# Calc_V4_Final.net
KiCad netlist of a schematic drawn in EAGLE
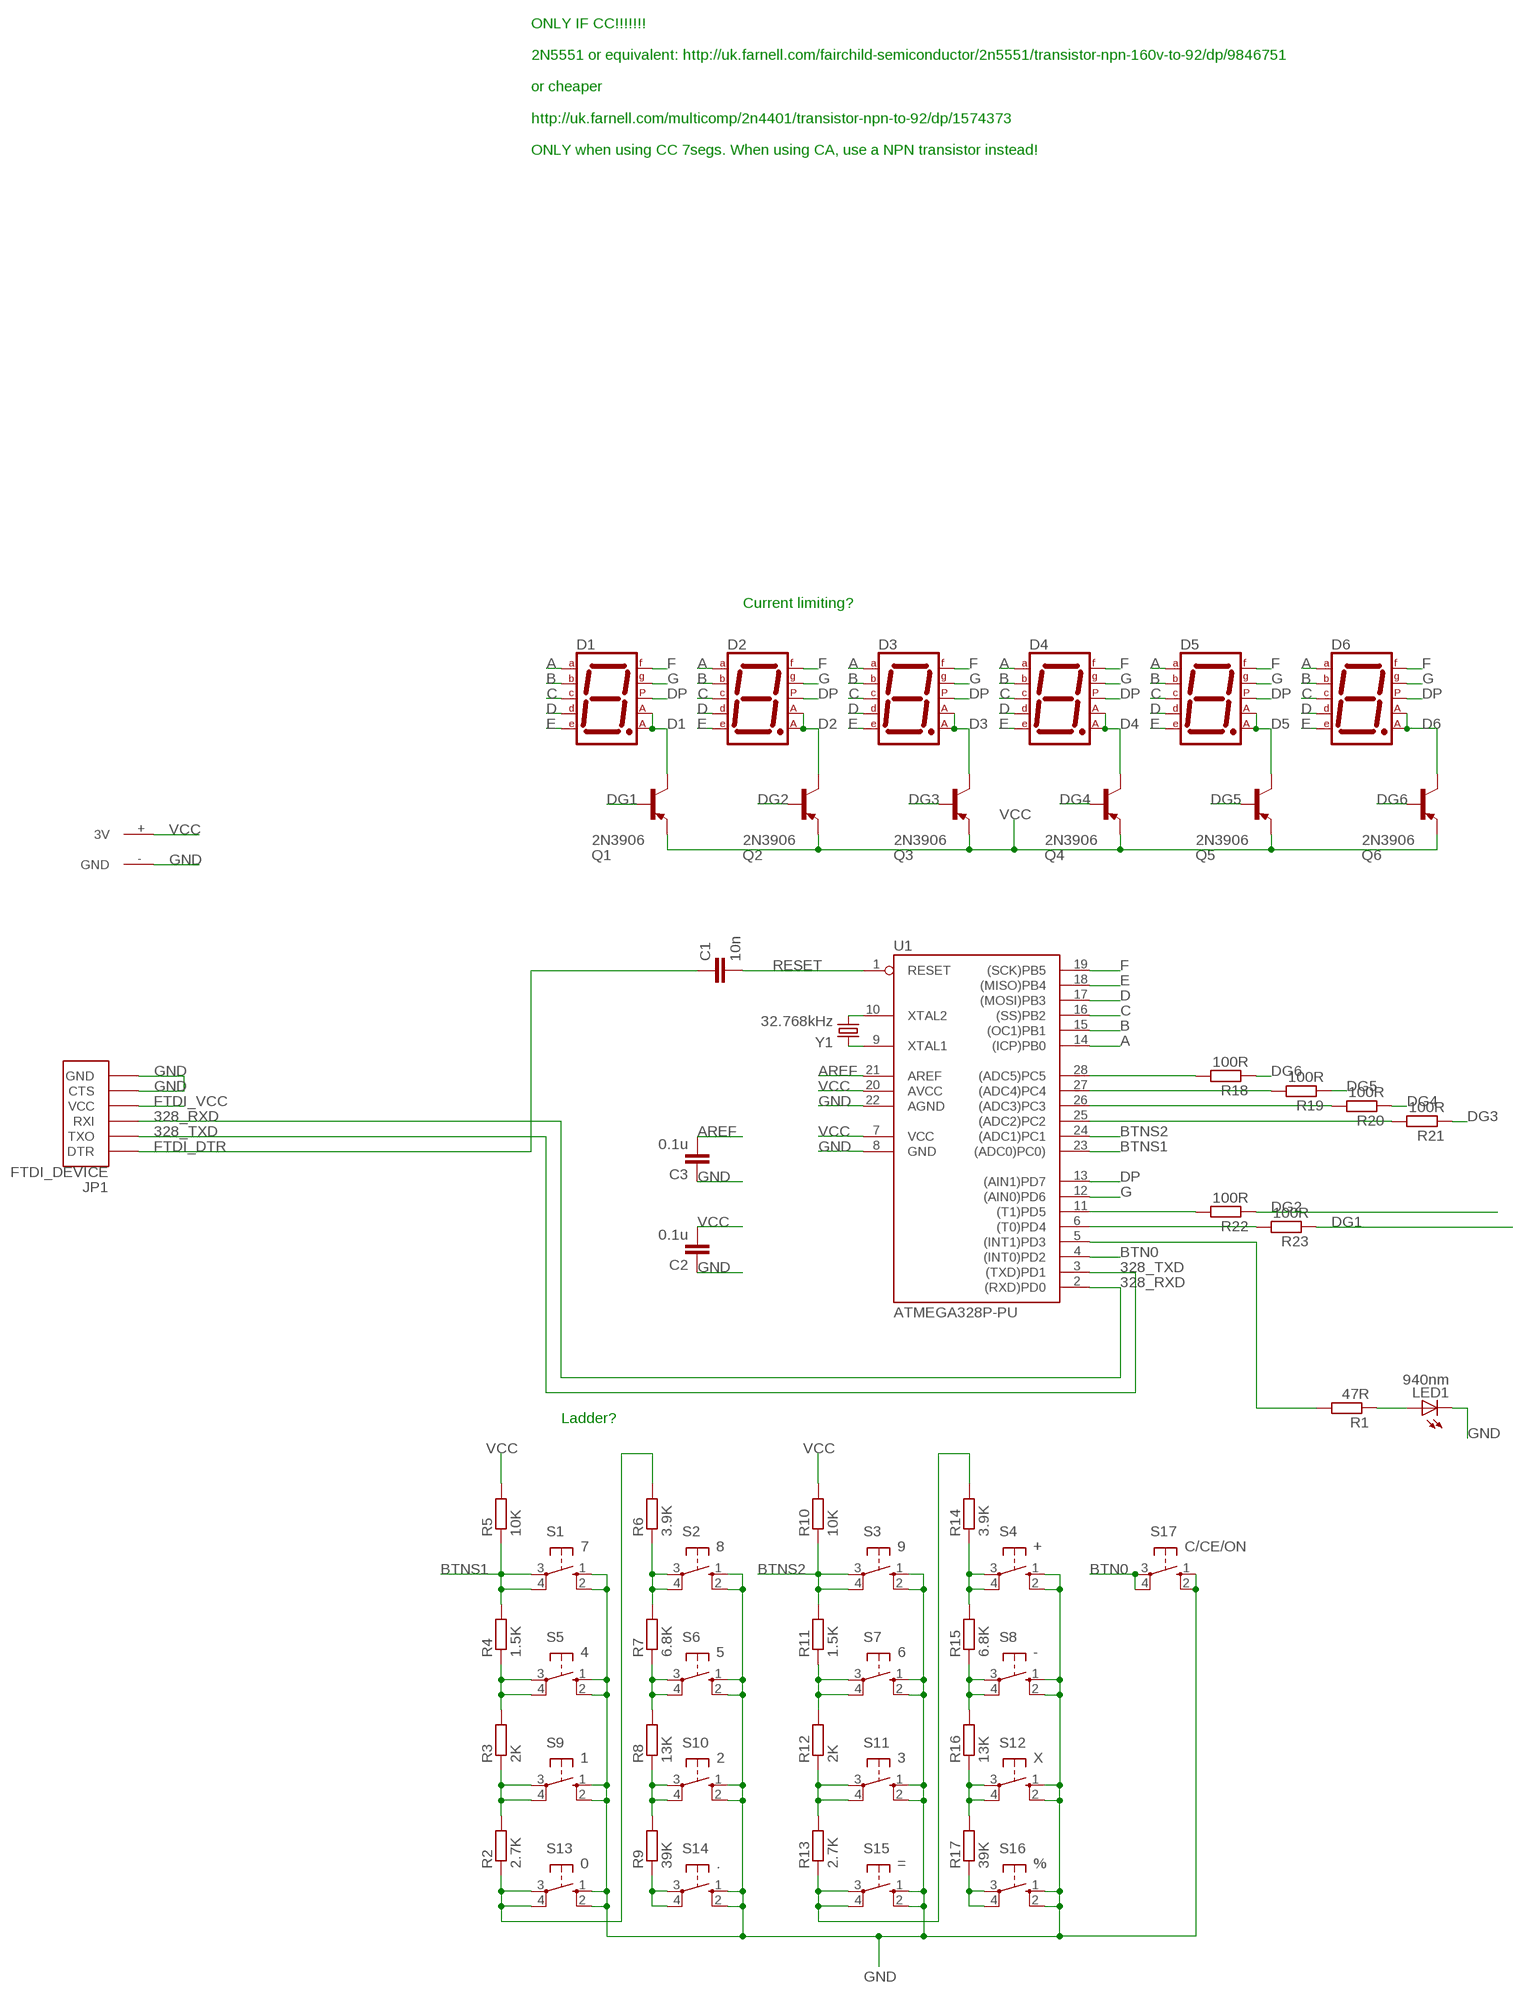
[diagram p0: schematic, sheet 1]

(export (version "E")
  (design (tool "Eeschema 10.0.6"))
  (components
    (comp (ref "C1")
      (value "10n")
      (footprint "eagle-import:C025-024X044")
      (libsource (lib "eagle-import") (part "C-EU025-024X044"))
    )
    (comp (ref "C2")
      (value "0.1u")
      (footprint "eagle-import:C025-024X044")
      (libsource (lib "eagle-import") (part "C-EU025-024X044"))
    )
    (comp (ref "C3")
      (value "0.1u")
      (footprint "eagle-import:C025-024X044")
      (libsource (lib "eagle-import") (part "C-EU025-024X044"))
    )
    (comp (ref "D1")
      (value "7SEG-MCA")
      (footprint "eagle-import:7SEG-7")
      (libsource (lib "eagle-import") (part "7SEG-MCA"))
    )
    (comp (ref "D2")
      (value "7SEG-MCA")
      (footprint "eagle-import:7SEG-7")
      (libsource (lib "eagle-import") (part "7SEG-MCA"))
    )
    (comp (ref "D3")
      (value "7SEG-MCA")
      (footprint "eagle-import:7SEG-7")
      (libsource (lib "eagle-import") (part "7SEG-MCA"))
    )
    (comp (ref "D4")
      (value "7SEG-MCA")
      (footprint "eagle-import:7SEG-7")
      (libsource (lib "eagle-import") (part "7SEG-MCA"))
    )
    (comp (ref "D5")
      (value "7SEG-MCA")
      (footprint "eagle-import:7SEG-7")
      (libsource (lib "eagle-import") (part "7SEG-MCA"))
    )
    (comp (ref "D6")
      (value "7SEG-MCA")
      (footprint "eagle-import:7SEG-7")
      (libsource (lib "eagle-import") (part "7SEG-MCA"))
    )
    (comp (ref "JP1")
      (value "FTDI_DEVICE")
      (footprint "eagle-import:FTDI_DEVICE_SIDE")
      (libsource (lib "eagle-import") (part "FTDI_DEVICE"))
    )
    (comp (ref "LED1")
      (value "940nm")
      (footprint "eagle-import:LED5MM")
      (libsource (lib "eagle-import") (part "LED5MM"))
    )
    (comp (ref "Q1")
      (value "2N3906")
      (footprint "eagle-import:TO92")
      (libsource (lib "eagle-import") (part "2N3906"))
    )
    (comp (ref "Q2")
      (value "2N3906")
      (footprint "eagle-import:TO92")
      (libsource (lib "eagle-import") (part "2N3906"))
    )
    (comp (ref "Q3")
      (value "2N3906")
      (footprint "eagle-import:TO92")
      (libsource (lib "eagle-import") (part "2N3906"))
    )
    (comp (ref "Q4")
      (value "2N3906")
      (footprint "eagle-import:TO92")
      (libsource (lib "eagle-import") (part "2N3906"))
    )
    (comp (ref "Q5")
      (value "2N3906")
      (footprint "eagle-import:TO92")
      (libsource (lib "eagle-import") (part "2N3906"))
    )
    (comp (ref "Q6")
      (value "2N3906")
      (footprint "eagle-import:TO92")
      (libsource (lib "eagle-import") (part "2N3906"))
    )
    (comp (ref "R1")
      (value "47R")
      (footprint "eagle-import:0207_10")
      (libsource (lib "eagle-import") (part "R-EU_0207/10"))
    )
    (comp (ref "R2")
      (value "2.7K")
      (footprint "eagle-import:0207_10")
      (libsource (lib "eagle-import") (part "R-EU_0207/10"))
    )
    (comp (ref "R3")
      (value "2K")
      (footprint "eagle-import:0207_10")
      (libsource (lib "eagle-import") (part "R-EU_0207/10"))
    )
    (comp (ref "R4")
      (value "1.5K")
      (footprint "eagle-import:0207_10")
      (libsource (lib "eagle-import") (part "R-EU_0207/10"))
    )
    (comp (ref "R5")
      (value "10K")
      (footprint "eagle-import:0207_10")
      (libsource (lib "eagle-import") (part "R-EU_0207/10"))
    )
    (comp (ref "R6")
      (value "3.9K")
      (footprint "eagle-import:0207_10")
      (libsource (lib "eagle-import") (part "R-EU_0207/10"))
    )
    (comp (ref "R7")
      (value "6.8K")
      (footprint "eagle-import:0207_10")
      (libsource (lib "eagle-import") (part "R-EU_0207/10"))
    )
    (comp (ref "R8")
      (value "13K")
      (footprint "eagle-import:0207_10")
      (libsource (lib "eagle-import") (part "R-EU_0207/10"))
    )
    (comp (ref "R9")
      (value "39K")
      (footprint "eagle-import:0207_10")
      (libsource (lib "eagle-import") (part "R-EU_0207/10"))
    )
    (comp (ref "R10")
      (value "10K")
      (footprint "eagle-import:0207_10")
      (libsource (lib "eagle-import") (part "R-EU_0207/10"))
    )
    (comp (ref "R11")
      (value "1.5K")
      (footprint "eagle-import:0207_10")
      (libsource (lib "eagle-import") (part "R-EU_0207/10"))
    )
    (comp (ref "R12")
      (value "2K")
      (footprint "eagle-import:0207_10")
      (libsource (lib "eagle-import") (part "R-EU_0207/10"))
    )
    (comp (ref "R13")
      (value "2.7K")
      (footprint "eagle-import:0207_10")
      (libsource (lib "eagle-import") (part "R-EU_0207/10"))
    )
    (comp (ref "R14")
      (value "3.9K")
      (footprint "eagle-import:0207_10")
      (libsource (lib "eagle-import") (part "R-EU_0207/10"))
    )
    (comp (ref "R15")
      (value "6.8K")
      (footprint "eagle-import:0207_10")
      (libsource (lib "eagle-import") (part "R-EU_0207/10"))
    )
    (comp (ref "R16")
      (value "13K")
      (footprint "eagle-import:0207_10")
      (libsource (lib "eagle-import") (part "R-EU_0207/10"))
    )
    (comp (ref "R17")
      (value "39K")
      (footprint "eagle-import:0207_10")
      (libsource (lib "eagle-import") (part "R-EU_0207/10"))
    )
    (comp (ref "R18")
      (value "100R")
      (footprint "eagle-import:0207_7")
      (libsource (lib "eagle-import") (part "R-EU_0207/7"))
    )
    (comp (ref "R19")
      (value "100R")
      (footprint "eagle-import:0207_7")
      (libsource (lib "eagle-import") (part "R-EU_0207/7"))
    )
    (comp (ref "R20")
      (value "100R")
      (footprint "eagle-import:0207_7")
      (libsource (lib "eagle-import") (part "R-EU_0207/7"))
    )
    (comp (ref "R21")
      (value "100R")
      (footprint "eagle-import:0207_7")
      (libsource (lib "eagle-import") (part "R-EU_0207/7"))
    )
    (comp (ref "R22")
      (value "100R")
      (footprint "eagle-import:0207_7")
      (libsource (lib "eagle-import") (part "R-EU_0207/7"))
    )
    (comp (ref "R23")
      (value "100R")
      (footprint "eagle-import:0207_7")
      (libsource (lib "eagle-import") (part "R-EU_0207/7"))
    )
    (comp (ref "S1")
      (value "7")
      (footprint "eagle-import:B3F-10XX")
      (fields (field (name "MPN") "B3F-1000"))
      (libsource (lib "eagle-import") (part "10-XX"))
    )
    (comp (ref "S2")
      (value "8")
      (footprint "eagle-import:B3F-10XX")
      (fields
        (field (name "MPN") "B3F-1000")
        (field (name "MPN_1") "B3F-1000")
        (field (name "OC_FARNELL") "176432")
        (field (name "OC_NEWARK") "36M3542")
      )
      (libsource (lib "eagle-import") (part "10-XX"))
    )
    (comp (ref "S3")
      (value "9")
      (footprint "eagle-import:B3F-10XX")
      (fields
        (field (name "MPN") "B3F-1000")
        (field (name "MPN_1") "B3F-1000")
        (field (name "OC_FARNELL") "176432")
        (field (name "OC_NEWARK") "36M3542")
      )
      (libsource (lib "eagle-import") (part "10-XX"))
    )
    (comp (ref "S4")
      (value "+")
      (footprint "eagle-import:B3F-10XX")
      (fields
        (field (name "MPN") "B3F-1000")
        (field (name "MPN_1") "B3F-1000")
        (field (name "OC_FARNELL") "176432")
        (field (name "OC_NEWARK") "36M3542")
      )
      (libsource (lib "eagle-import") (part "10-XX"))
    )
    (comp (ref "S5")
      (value "4")
      (footprint "eagle-import:B3F-10XX")
      (fields
        (field (name "MPN") "B3F-1000")
        (field (name "MPN_1") "B3F-1000")
        (field (name "OC_FARNELL") "176432")
        (field (name "OC_NEWARK") "36M3542")
      )
      (libsource (lib "eagle-import") (part "10-XX"))
    )
    (comp (ref "S6")
      (value "5")
      (footprint "eagle-import:B3F-10XX")
      (fields
        (field (name "MPN") "B3F-1000")
        (field (name "MPN_1") "B3F-1000")
        (field (name "OC_FARNELL") "176432")
        (field (name "OC_NEWARK") "36M3542")
      )
      (libsource (lib "eagle-import") (part "10-XX"))
    )
    (comp (ref "S7")
      (value "6")
      (footprint "eagle-import:B3F-10XX")
      (fields
        (field (name "MPN") "B3F-1000")
        (field (name "MPN_1") "B3F-1000")
        (field (name "OC_FARNELL") "176432")
        (field (name "OC_NEWARK") "36M3542")
      )
      (libsource (lib "eagle-import") (part "10-XX"))
    )
    (comp (ref "S8")
      (value "-")
      (footprint "eagle-import:B3F-10XX")
      (fields
        (field (name "MPN") "B3F-1000")
        (field (name "MPN_1") "B3F-1000")
        (field (name "OC_FARNELL") "176432")
        (field (name "OC_NEWARK") "36M3542")
      )
      (libsource (lib "eagle-import") (part "10-XX"))
    )
    (comp (ref "S9")
      (value "1")
      (footprint "eagle-import:B3F-10XX")
      (fields (field (name "MPN") "B3F-1000"))
      (libsource (lib "eagle-import") (part "10-XX"))
    )
    (comp (ref "S10")
      (value "2")
      (footprint "eagle-import:B3F-10XX")
      (fields
        (field (name "MPN") "B3F-1000")
        (field (name "MPN_1") "B3F-1000")
        (field (name "OC_FARNELL") "176432")
        (field (name "OC_NEWARK") "36M3542")
      )
      (libsource (lib "eagle-import") (part "10-XX"))
    )
    (comp (ref "S11")
      (value "3")
      (footprint "eagle-import:B3F-10XX")
      (fields
        (field (name "MPN") "B3F-1000")
        (field (name "MPN_1") "B3F-1000")
        (field (name "OC_FARNELL") "176432")
        (field (name "OC_NEWARK") "36M3542")
      )
      (libsource (lib "eagle-import") (part "10-XX"))
    )
    (comp (ref "S12")
      (value "X")
      (footprint "eagle-import:B3F-10XX")
      (fields
        (field (name "MPN") "B3F-1000")
        (field (name "MPN_1") "B3F-1000")
        (field (name "OC_FARNELL") "176432")
        (field (name "OC_NEWARK") "36M3542")
      )
      (libsource (lib "eagle-import") (part "10-XX"))
    )
    (comp (ref "S13")
      (value "0")
      (footprint "eagle-import:B3F-10XX")
      (fields
        (field (name "MPN") "B3F-1000")
        (field (name "MPN_1") "B3F-1000")
        (field (name "OC_FARNELL") "176432")
        (field (name "OC_NEWARK") "36M3542")
      )
      (libsource (lib "eagle-import") (part "10-XX"))
    )
    (comp (ref "S14")
      (value ".")
      (footprint "eagle-import:B3F-10XX")
      (fields
        (field (name "MPN") "B3F-1000")
        (field (name "MPN_1") "B3F-1000")
        (field (name "OC_FARNELL") "176432")
        (field (name "OC_NEWARK") "36M3542")
      )
      (libsource (lib "eagle-import") (part "10-XX"))
    )
    (comp (ref "S15")
      (value "=")
      (footprint "eagle-import:B3F-10XX")
      (fields
        (field (name "MPN") "B3F-1000")
        (field (name "MPN_1") "B3F-1000")
        (field (name "OC_FARNELL") "176432")
        (field (name "OC_NEWARK") "36M3542")
      )
      (libsource (lib "eagle-import") (part "10-XX"))
    )
    (comp (ref "S16")
      (value "%")
      (footprint "eagle-import:B3F-10XX")
      (fields
        (field (name "MPN") "B3F-1000")
        (field (name "MPN_1") "B3F-1000")
        (field (name "OC_FARNELL") "176432")
        (field (name "OC_NEWARK") "36M3542")
      )
      (libsource (lib "eagle-import") (part "10-XX"))
    )
    (comp (ref "S17")
      (value "C/CE/ON")
      (footprint "eagle-import:B3F-10XX")
      (fields
        (field (name "MPN") "B3F-1000")
        (field (name "MPN_1") "B3F-1000")
        (field (name "OC_FARNELL") "176432")
        (field (name "OC_NEWARK") "36M3542")
      )
      (libsource (lib "eagle-import") (part "10-XX"))
    )
    (comp (ref "U$1")
      (value "AAA-BATTERY")
      (footprint "eagle-import:AAA-BATTERY-CONTACT")
      (libsource (lib "eagle-import") (part "AAA-BATTERY"))
    )
    (comp (ref "U1")
      (value "ATMEGA328P-PU")
      (footprint "eagle-import:DIL28-3")
      (libsource (lib "eagle-import") (part "ATMEGA328P-PU"))
    )
    (comp (ref "Y1")
      (value "32.768kHz")
      (footprint "eagle-import:TC26HEZ")
      (libsource (lib "eagle-import") (part "CRYSTALTC26H_EZ"))
    )
  )
  (nets
    (net (code "1") (name "/328_RXD") (class "Default")
      (node (ref "JP1") (pin "P$3") (pinfunction "RXI_P$3") (pintype "bidirectional"))
      (node (ref "U1") (pin "2") (pinfunction "(RXD)PD0_2") (pintype "bidirectional"))
    )
    (net (code "2") (name "/328_TXD") (class "Default")
      (node (ref "JP1") (pin "P$2") (pinfunction "TXO_P$2") (pintype "bidirectional"))
      (node (ref "U1") (pin "3") (pinfunction "(TXD)PD1_3") (pintype "bidirectional"))
    )
    (net (code "3") (name "/A") (class "Default")
      (node (ref "D1") (pin "10") (pinfunction "A_10") (pintype "passive"))
      (node (ref "D2") (pin "10") (pinfunction "A_10") (pintype "passive"))
      (node (ref "D3") (pin "10") (pinfunction "A_10") (pintype "passive"))
      (node (ref "D4") (pin "10") (pinfunction "A_10") (pintype "passive"))
      (node (ref "D5") (pin "10") (pinfunction "A_10") (pintype "passive"))
      (node (ref "D6") (pin "10") (pinfunction "A_10") (pintype "passive"))
      (node (ref "U1") (pin "14") (pinfunction "(ICP)PB0_14") (pintype "bidirectional"))
    )
    (net (code "4") (name "/AREF") (class "Default")
      (node (ref "C3") (pin "2") (pinfunction "2_2") (pintype "passive"))
      (node (ref "U1") (pin "21") (pinfunction "AREF_21") (pintype "passive"))
    )
    (net (code "5") (name "/B") (class "Default")
      (node (ref "D1") (pin "9") (pinfunction "B_9") (pintype "passive"))
      (node (ref "D2") (pin "9") (pinfunction "B_9") (pintype "passive"))
      (node (ref "D3") (pin "9") (pinfunction "B_9") (pintype "passive"))
      (node (ref "D4") (pin "9") (pinfunction "B_9") (pintype "passive"))
      (node (ref "D5") (pin "9") (pinfunction "B_9") (pintype "passive"))
      (node (ref "D6") (pin "9") (pinfunction "B_9") (pintype "passive"))
      (node (ref "U1") (pin "15") (pinfunction "(OC1)PB1_15") (pintype "bidirectional"))
    )
    (net (code "6") (name "/BTN0") (class "Default")
      (node (ref "S17") (pin "3") (pinfunction "P_3") (pintype "passive"))
      (node (ref "S17") (pin "4") (pinfunction "P1_4") (pintype "passive"))
      (node (ref "U1") (pin "4") (pinfunction "(INT0)PD2_4") (pintype "bidirectional"))
    )
    (net (code "7") (name "/BTNS1") (class "Default")
      (node (ref "R4") (pin "2") (pinfunction "2_2") (pintype "passive"))
      (node (ref "R5") (pin "1") (pinfunction "1_1") (pintype "passive"))
      (node (ref "S1") (pin "3") (pinfunction "P_3") (pintype "passive"))
      (node (ref "S1") (pin "4") (pinfunction "P1_4") (pintype "passive"))
      (node (ref "U1") (pin "23") (pinfunction "(ADC0)PC0)_23") (pintype "bidirectional"))
    )
    (net (code "8") (name "/BTNS2") (class "Default")
      (node (ref "R10") (pin "1") (pinfunction "1_1") (pintype "passive"))
      (node (ref "R11") (pin "2") (pinfunction "2_2") (pintype "passive"))
      (node (ref "S3") (pin "3") (pinfunction "P_3") (pintype "passive"))
      (node (ref "S3") (pin "4") (pinfunction "P1_4") (pintype "passive"))
      (node (ref "U1") (pin "24") (pinfunction "(ADC1)PC1_24") (pintype "bidirectional"))
    )
    (net (code "9") (name "/C") (class "Default")
      (node (ref "D1") (pin "8") (pinfunction "C_8") (pintype "passive"))
      (node (ref "D2") (pin "8") (pinfunction "C_8") (pintype "passive"))
      (node (ref "D3") (pin "8") (pinfunction "C_8") (pintype "passive"))
      (node (ref "D4") (pin "8") (pinfunction "C_8") (pintype "passive"))
      (node (ref "D5") (pin "8") (pinfunction "C_8") (pintype "passive"))
      (node (ref "D6") (pin "8") (pinfunction "C_8") (pintype "passive"))
      (node (ref "U1") (pin "16") (pinfunction "(SS)PB2_16") (pintype "bidirectional"))
    )
    (net (code "10") (name "/D") (class "Default")
      (node (ref "D1") (pin "5") (pinfunction "D_5") (pintype "passive"))
      (node (ref "D2") (pin "5") (pinfunction "D_5") (pintype "passive"))
      (node (ref "D3") (pin "5") (pinfunction "D_5") (pintype "passive"))
      (node (ref "D4") (pin "5") (pinfunction "D_5") (pintype "passive"))
      (node (ref "D5") (pin "5") (pinfunction "D_5") (pintype "passive"))
      (node (ref "D6") (pin "5") (pinfunction "D_5") (pintype "passive"))
      (node (ref "U1") (pin "17") (pinfunction "(MOSI)PB3_17") (pintype "bidirectional"))
    )
    (net (code "11") (name "/D1") (class "Default")
      (node (ref "D1") (pin "1") (pinfunction "CA1_1") (pintype "passive"))
      (node (ref "D1") (pin "6") (pinfunction "CA2_6") (pintype "passive"))
      (node (ref "Q1") (pin "1") (pinfunction "C_1") (pintype "passive"))
    )
    (net (code "12") (name "/D2") (class "Default")
      (node (ref "D2") (pin "1") (pinfunction "CA1_1") (pintype "passive"))
      (node (ref "D2") (pin "6") (pinfunction "CA2_6") (pintype "passive"))
      (node (ref "Q2") (pin "1") (pinfunction "C_1") (pintype "passive"))
    )
    (net (code "13") (name "/D3") (class "Default")
      (node (ref "D3") (pin "1") (pinfunction "CA1_1") (pintype "passive"))
      (node (ref "D3") (pin "6") (pinfunction "CA2_6") (pintype "passive"))
      (node (ref "Q3") (pin "1") (pinfunction "C_1") (pintype "passive"))
    )
    (net (code "14") (name "/D4") (class "Default")
      (node (ref "D4") (pin "1") (pinfunction "CA1_1") (pintype "passive"))
      (node (ref "D4") (pin "6") (pinfunction "CA2_6") (pintype "passive"))
      (node (ref "Q4") (pin "1") (pinfunction "C_1") (pintype "passive"))
    )
    (net (code "15") (name "/D5") (class "Default")
      (node (ref "D5") (pin "1") (pinfunction "CA1_1") (pintype "passive"))
      (node (ref "D5") (pin "6") (pinfunction "CA2_6") (pintype "passive"))
      (node (ref "Q5") (pin "1") (pinfunction "C_1") (pintype "passive"))
    )
    (net (code "16") (name "/D6") (class "Default")
      (node (ref "D6") (pin "1") (pinfunction "CA1_1") (pintype "passive"))
      (node (ref "D6") (pin "6") (pinfunction "CA2_6") (pintype "passive"))
      (node (ref "Q6") (pin "1") (pinfunction "C_1") (pintype "passive"))
    )
    (net (code "17") (name "/DG1") (class "Default")
      (node (ref "Q1") (pin "2") (pinfunction "B_2") (pintype "passive"))
      (node (ref "R23") (pin "1") (pinfunction "1_1") (pintype "passive"))
    )
    (net (code "18") (name "/DG2") (class "Default")
      (node (ref "Q2") (pin "2") (pinfunction "B_2") (pintype "passive"))
      (node (ref "R22") (pin "1") (pinfunction "1_1") (pintype "passive"))
    )
    (net (code "19") (name "/DG3") (class "Default")
      (node (ref "Q3") (pin "2") (pinfunction "B_2") (pintype "passive"))
      (node (ref "R21") (pin "1") (pinfunction "1_1") (pintype "passive"))
    )
    (net (code "20") (name "/DG4") (class "Default")
      (node (ref "Q4") (pin "2") (pinfunction "B_2") (pintype "passive"))
      (node (ref "R20") (pin "1") (pinfunction "1_1") (pintype "passive"))
    )
    (net (code "21") (name "/DG5") (class "Default")
      (node (ref "Q5") (pin "2") (pinfunction "B_2") (pintype "passive"))
      (node (ref "R19") (pin "1") (pinfunction "1_1") (pintype "passive"))
    )
    (net (code "22") (name "/DG6") (class "Default")
      (node (ref "Q6") (pin "2") (pinfunction "B_2") (pintype "passive"))
      (node (ref "R18") (pin "1") (pinfunction "1_1") (pintype "passive"))
    )
    (net (code "23") (name "/DP") (class "Default")
      (node (ref "D1") (pin "7") (pinfunction "DP_7") (pintype "passive"))
      (node (ref "D2") (pin "7") (pinfunction "DP_7") (pintype "passive"))
      (node (ref "D3") (pin "7") (pinfunction "DP_7") (pintype "passive"))
      (node (ref "D4") (pin "7") (pinfunction "DP_7") (pintype "passive"))
      (node (ref "D5") (pin "7") (pinfunction "DP_7") (pintype "passive"))
      (node (ref "D6") (pin "7") (pinfunction "DP_7") (pintype "passive"))
      (node (ref "U1") (pin "13") (pinfunction "(AIN1)PD7_13") (pintype "bidirectional"))
    )
    (net (code "24") (name "/E") (class "Default")
      (node (ref "D1") (pin "4") (pinfunction "E_4") (pintype "passive"))
      (node (ref "D2") (pin "4") (pinfunction "E_4") (pintype "passive"))
      (node (ref "D3") (pin "4") (pinfunction "E_4") (pintype "passive"))
      (node (ref "D4") (pin "4") (pinfunction "E_4") (pintype "passive"))
      (node (ref "D5") (pin "4") (pinfunction "E_4") (pintype "passive"))
      (node (ref "D6") (pin "4") (pinfunction "E_4") (pintype "passive"))
      (node (ref "U1") (pin "18") (pinfunction "(MISO)PB4_18") (pintype "bidirectional"))
    )
    (net (code "25") (name "/F") (class "Default")
      (node (ref "D1") (pin "2") (pinfunction "F_2") (pintype "passive"))
      (node (ref "D2") (pin "2") (pinfunction "F_2") (pintype "passive"))
      (node (ref "D3") (pin "2") (pinfunction "F_2") (pintype "passive"))
      (node (ref "D4") (pin "2") (pinfunction "F_2") (pintype "passive"))
      (node (ref "D5") (pin "2") (pinfunction "F_2") (pintype "passive"))
      (node (ref "D6") (pin "2") (pinfunction "F_2") (pintype "passive"))
      (node (ref "U1") (pin "19") (pinfunction "(SCK)PB5_19") (pintype "bidirectional"))
    )
    (net (code "26") (name "/FTDI_DTR") (class "Default")
      (node (ref "C1") (pin "1") (pinfunction "1_1") (pintype "passive"))
      (node (ref "JP1") (pin "P$1") (pinfunction "DTR_P$1") (pintype "bidirectional"))
    )
    (net (code "27") (name "/FTDI_VCC") (class "Default")
      (node (ref "JP1") (pin "P$4") (pinfunction "VCC_P$4") (pintype "bidirectional"))
    )
    (net (code "28") (name "/G") (class "Default")
      (node (ref "D1") (pin "3") (pinfunction "G_3") (pintype "passive"))
      (node (ref "D2") (pin "3") (pinfunction "G_3") (pintype "passive"))
      (node (ref "D3") (pin "3") (pinfunction "G_3") (pintype "passive"))
      (node (ref "D4") (pin "3") (pinfunction "G_3") (pintype "passive"))
      (node (ref "D5") (pin "3") (pinfunction "G_3") (pintype "passive"))
      (node (ref "D6") (pin "3") (pinfunction "G_3") (pintype "passive"))
      (node (ref "U1") (pin "12") (pinfunction "(AIN0)PD6_12") (pintype "bidirectional"))
    )
    (net (code "29") (name "/GND") (class "Default")
      (node (ref "C2") (pin "1") (pinfunction "1_1") (pintype "passive"))
      (node (ref "C3") (pin "1") (pinfunction "1_1") (pintype "passive"))
      (node (ref "JP1") (pin "P$5") (pinfunction "CTS_P$5") (pintype "bidirectional"))
      (node (ref "JP1") (pin "P$6") (pinfunction "GND_P$6") (pintype "bidirectional"))
      (node (ref "LED1") (pin "K") (pinfunction "C_K") (pintype "passive"))
      (node (ref "S1") (pin "1") (pinfunction "S_1") (pintype "passive"))
      (node (ref "S1") (pin "2") (pinfunction "S1_2") (pintype "passive"))
      (node (ref "S10") (pin "1") (pinfunction "S_1") (pintype "passive"))
      (node (ref "S10") (pin "2") (pinfunction "S1_2") (pintype "passive"))
      (node (ref "S11") (pin "1") (pinfunction "S_1") (pintype "passive"))
      (node (ref "S11") (pin "2") (pinfunction "S1_2") (pintype "passive"))
      (node (ref "S12") (pin "1") (pinfunction "S_1") (pintype "passive"))
      (node (ref "S12") (pin "2") (pinfunction "S1_2") (pintype "passive"))
      (node (ref "S13") (pin "1") (pinfunction "S_1") (pintype "passive"))
      (node (ref "S13") (pin "2") (pinfunction "S1_2") (pintype "passive"))
      (node (ref "S14") (pin "1") (pinfunction "S_1") (pintype "passive"))
      (node (ref "S14") (pin "2") (pinfunction "S1_2") (pintype "passive"))
      (node (ref "S15") (pin "1") (pinfunction "S_1") (pintype "passive"))
      (node (ref "S15") (pin "2") (pinfunction "S1_2") (pintype "passive"))
      (node (ref "S16") (pin "1") (pinfunction "S_1") (pintype "passive"))
      (node (ref "S16") (pin "2") (pinfunction "S1_2") (pintype "passive"))
      (node (ref "S17") (pin "1") (pinfunction "S_1") (pintype "passive"))
      (node (ref "S17") (pin "2") (pinfunction "S1_2") (pintype "passive"))
      (node (ref "S2") (pin "1") (pinfunction "S_1") (pintype "passive"))
      (node (ref "S2") (pin "2") (pinfunction "S1_2") (pintype "passive"))
      (node (ref "S3") (pin "1") (pinfunction "S_1") (pintype "passive"))
      (node (ref "S3") (pin "2") (pinfunction "S1_2") (pintype "passive"))
      (node (ref "S4") (pin "1") (pinfunction "S_1") (pintype "passive"))
      (node (ref "S4") (pin "2") (pinfunction "S1_2") (pintype "passive"))
      (node (ref "S5") (pin "1") (pinfunction "S_1") (pintype "passive"))
      (node (ref "S5") (pin "2") (pinfunction "S1_2") (pintype "passive"))
      (node (ref "S6") (pin "1") (pinfunction "S_1") (pintype "passive"))
      (node (ref "S6") (pin "2") (pinfunction "S1_2") (pintype "passive"))
      (node (ref "S7") (pin "1") (pinfunction "S_1") (pintype "passive"))
      (node (ref "S7") (pin "2") (pinfunction "S1_2") (pintype "passive"))
      (node (ref "S8") (pin "1") (pinfunction "S_1") (pintype "passive"))
      (node (ref "S8") (pin "2") (pinfunction "S1_2") (pintype "passive"))
      (node (ref "S9") (pin "1") (pinfunction "S_1") (pintype "passive"))
      (node (ref "S9") (pin "2") (pinfunction "S1_2") (pintype "passive"))
      (node (ref "U$1") (pin "-") (pinfunction "GND_-") (pintype "bidirectional"))
      (node (ref "U1") (pin "22") (pinfunction "AGND_22") (pintype "power_in"))
      (node (ref "U1") (pin "8") (pinfunction "GND_8") (pintype "power_in"))
    )
    (net (code "30") (name "/RESET") (class "Default")
      (node (ref "C1") (pin "2") (pinfunction "2_2") (pintype "passive"))
      (node (ref "U1") (pin "1") (pinfunction "RESET_1") (pintype "input"))
    )
    (net (code "31") (name "/VCC") (class "Default")
      (node (ref "C2") (pin "2") (pinfunction "2_2") (pintype "passive"))
      (node (ref "Q1") (pin "3") (pinfunction "E_3") (pintype "passive"))
      (node (ref "Q2") (pin "3") (pinfunction "E_3") (pintype "passive"))
      (node (ref "Q3") (pin "3") (pinfunction "E_3") (pintype "passive"))
      (node (ref "Q4") (pin "3") (pinfunction "E_3") (pintype "passive"))
      (node (ref "Q5") (pin "3") (pinfunction "E_3") (pintype "passive"))
      (node (ref "Q6") (pin "3") (pinfunction "E_3") (pintype "passive"))
      (node (ref "R10") (pin "2") (pinfunction "2_2") (pintype "passive"))
      (node (ref "R5") (pin "2") (pinfunction "2_2") (pintype "passive"))
      (node (ref "U$1") (pin "+") (pinfunction "3V_+") (pintype "bidirectional"))
      (node (ref "U1") (pin "20") (pinfunction "AVCC_20") (pintype "power_in"))
      (node (ref "U1") (pin "7") (pinfunction "VCC_7") (pintype "power_in"))
    )
    (net (code "32") (name "Net-(LED1-PadA)") (class "Default")
      (node (ref "LED1") (pin "A") (pinfunction "A_A") (pintype "passive"))
      (node (ref "R1") (pin "1") (pinfunction "1_1") (pintype "passive"))
    )
    (net (code "33") (name "Net-(S2-P)") (class "Default")
      (node (ref "R6") (pin "1") (pinfunction "1_1") (pintype "passive"))
      (node (ref "R7") (pin "2") (pinfunction "2_2") (pintype "passive"))
      (node (ref "S2") (pin "3") (pinfunction "P_3") (pintype "passive"))
      (node (ref "S2") (pin "4") (pinfunction "P1_4") (pintype "passive"))
    )
    (net (code "34") (name "Net-(S4-P)") (class "Default")
      (node (ref "R14") (pin "1") (pinfunction "1_1") (pintype "passive"))
      (node (ref "R15") (pin "2") (pinfunction "2_2") (pintype "passive"))
      (node (ref "S4") (pin "3") (pinfunction "P_3") (pintype "passive"))
      (node (ref "S4") (pin "4") (pinfunction "P1_4") (pintype "passive"))
    )
    (net (code "35") (name "Net-(S5-P)") (class "Default")
      (node (ref "R3") (pin "2") (pinfunction "2_2") (pintype "passive"))
      (node (ref "R4") (pin "1") (pinfunction "1_1") (pintype "passive"))
      (node (ref "S5") (pin "3") (pinfunction "P_3") (pintype "passive"))
      (node (ref "S5") (pin "4") (pinfunction "P1_4") (pintype "passive"))
    )
    (net (code "36") (name "Net-(S6-P)") (class "Default")
      (node (ref "R7") (pin "1") (pinfunction "1_1") (pintype "passive"))
      (node (ref "R8") (pin "2") (pinfunction "2_2") (pintype "passive"))
      (node (ref "S6") (pin "3") (pinfunction "P_3") (pintype "passive"))
      (node (ref "S6") (pin "4") (pinfunction "P1_4") (pintype "passive"))
    )
    (net (code "37") (name "Net-(S7-P)") (class "Default")
      (node (ref "R11") (pin "1") (pinfunction "1_1") (pintype "passive"))
      (node (ref "R12") (pin "2") (pinfunction "2_2") (pintype "passive"))
      (node (ref "S7") (pin "3") (pinfunction "P_3") (pintype "passive"))
      (node (ref "S7") (pin "4") (pinfunction "P1_4") (pintype "passive"))
    )
    (net (code "38") (name "Net-(S8-P)") (class "Default")
      (node (ref "R15") (pin "1") (pinfunction "1_1") (pintype "passive"))
      (node (ref "R16") (pin "2") (pinfunction "2_2") (pintype "passive"))
      (node (ref "S8") (pin "3") (pinfunction "P_3") (pintype "passive"))
      (node (ref "S8") (pin "4") (pinfunction "P1_4") (pintype "passive"))
    )
    (net (code "39") (name "Net-(S9-P)") (class "Default")
      (node (ref "R2") (pin "2") (pinfunction "2_2") (pintype "passive"))
      (node (ref "R3") (pin "1") (pinfunction "1_1") (pintype "passive"))
      (node (ref "S9") (pin "3") (pinfunction "P_3") (pintype "passive"))
      (node (ref "S9") (pin "4") (pinfunction "P1_4") (pintype "passive"))
    )
    (net (code "40") (name "Net-(S10-P)") (class "Default")
      (node (ref "R8") (pin "1") (pinfunction "1_1") (pintype "passive"))
      (node (ref "R9") (pin "2") (pinfunction "2_2") (pintype "passive"))
      (node (ref "S10") (pin "3") (pinfunction "P_3") (pintype "passive"))
      (node (ref "S10") (pin "4") (pinfunction "P1_4") (pintype "passive"))
    )
    (net (code "41") (name "Net-(S11-P)") (class "Default")
      (node (ref "R12") (pin "1") (pinfunction "1_1") (pintype "passive"))
      (node (ref "R13") (pin "2") (pinfunction "2_2") (pintype "passive"))
      (node (ref "S11") (pin "3") (pinfunction "P_3") (pintype "passive"))
      (node (ref "S11") (pin "4") (pinfunction "P1_4") (pintype "passive"))
    )
    (net (code "42") (name "Net-(S12-P)") (class "Default")
      (node (ref "R16") (pin "1") (pinfunction "1_1") (pintype "passive"))
      (node (ref "R17") (pin "2") (pinfunction "2_2") (pintype "passive"))
      (node (ref "S12") (pin "3") (pinfunction "P_3") (pintype "passive"))
      (node (ref "S12") (pin "4") (pinfunction "P1_4") (pintype "passive"))
    )
    (net (code "43") (name "Net-(S13-P)") (class "Default")
      (node (ref "R2") (pin "1") (pinfunction "1_1") (pintype "passive"))
      (node (ref "R6") (pin "2") (pinfunction "2_2") (pintype "passive"))
      (node (ref "S13") (pin "3") (pinfunction "P_3") (pintype "passive"))
      (node (ref "S13") (pin "4") (pinfunction "P1_4") (pintype "passive"))
    )
    (net (code "44") (name "Net-(S14-P)") (class "Default")
      (node (ref "R9") (pin "1") (pinfunction "1_1") (pintype "passive"))
      (node (ref "S14") (pin "3") (pinfunction "P_3") (pintype "passive"))
      (node (ref "S14") (pin "4") (pinfunction "P1_4") (pintype "passive"))
    )
    (net (code "45") (name "Net-(S15-P)") (class "Default")
      (node (ref "R13") (pin "1") (pinfunction "1_1") (pintype "passive"))
      (node (ref "R14") (pin "2") (pinfunction "2_2") (pintype "passive"))
      (node (ref "S15") (pin "3") (pinfunction "P_3") (pintype "passive"))
      (node (ref "S15") (pin "4") (pinfunction "P1_4") (pintype "passive"))
    )
    (net (code "46") (name "Net-(S16-P)") (class "Default")
      (node (ref "R17") (pin "1") (pinfunction "1_1") (pintype "passive"))
      (node (ref "S16") (pin "3") (pinfunction "P_3") (pintype "passive"))
      (node (ref "S16") (pin "4") (pinfunction "P1_4") (pintype "passive"))
    )
    (net (code "47") (name "Net-(U1-(ADC2)PC2)") (class "Default")
      (node (ref "R21") (pin "2") (pinfunction "2_2") (pintype "passive"))
      (node (ref "U1") (pin "25") (pinfunction "(ADC2)PC2_25") (pintype "bidirectional"))
    )
    (net (code "48") (name "Net-(U1-(ADC3)PC3)") (class "Default")
      (node (ref "R20") (pin "2") (pinfunction "2_2") (pintype "passive"))
      (node (ref "U1") (pin "26") (pinfunction "(ADC3)PC3_26") (pintype "bidirectional"))
    )
    (net (code "49") (name "Net-(U1-(ADC4)PC4)") (class "Default")
      (node (ref "R19") (pin "2") (pinfunction "2_2") (pintype "passive"))
      (node (ref "U1") (pin "27") (pinfunction "(ADC4)PC4_27") (pintype "bidirectional"))
    )
    (net (code "50") (name "Net-(U1-(ADC5)PC5)") (class "Default")
      (node (ref "R18") (pin "2") (pinfunction "2_2") (pintype "passive"))
      (node (ref "U1") (pin "28") (pinfunction "(ADC5)PC5_28") (pintype "bidirectional"))
    )
    (net (code "51") (name "Net-(U1-(INT1)PD3)") (class "Default")
      (node (ref "R1") (pin "2") (pinfunction "2_2") (pintype "passive"))
      (node (ref "U1") (pin "5") (pinfunction "(INT1)PD3_5") (pintype "bidirectional"))
    )
    (net (code "52") (name "Net-(U1-(T0)PD4)") (class "Default")
      (node (ref "R23") (pin "2") (pinfunction "2_2") (pintype "passive"))
      (node (ref "U1") (pin "6") (pinfunction "(T0)PD4_6") (pintype "bidirectional"))
    )
    (net (code "53") (name "Net-(U1-(T1)PD5)") (class "Default")
      (node (ref "R22") (pin "2") (pinfunction "2_2") (pintype "passive"))
      (node (ref "U1") (pin "11") (pinfunction "(T1)PD5_11") (pintype "bidirectional"))
    )
    (net (code "54") (name "Net-(U1-XTAL1)") (class "Default")
      (node (ref "U1") (pin "9") (pinfunction "XTAL1_9") (pintype "bidirectional"))
      (node (ref "Y1") (pin "2") (pinfunction "2_2") (pintype "passive"))
    )
    (net (code "55") (name "Net-(U1-XTAL2)") (class "Default")
      (node (ref "U1") (pin "10") (pinfunction "XTAL2_10") (pintype "bidirectional"))
      (node (ref "Y1") (pin "1") (pinfunction "1_1") (pintype "passive"))
    )
  )
)
